# Connector.net
KiCad netlist of a schematic drawn in Altium Designer
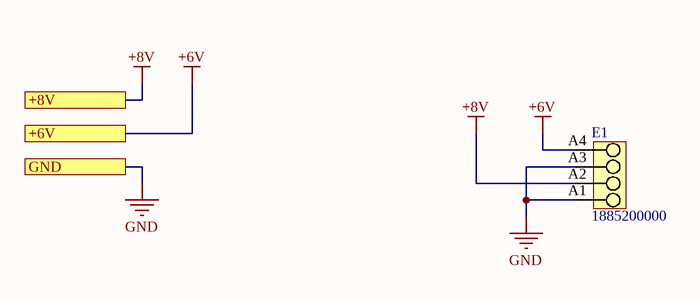
[diagram p0: Connector.SchDoc]

(export (version "E")
  (design (tool "Eeschema 10.0.6"))
  (components
    (comp (ref "E1")
      (value "1885200000")
      (footprint "LSF_SMT_3_5_135_04")
      (description "OMNIMATE Signal - series LSF")
      (fields (field (name "MANUFACTURER") "Weidmueller"))
      (libsource (lib "Altium Content Vault") (part "Terminal_04_1x04"))
    )
  )
  (nets
    (net (code "1") (name "+6V") (class "Default")
      (node (ref "E1") (pin "A4") (pinfunction "A4_A4") (pintype "passive"))
    )
    (net (code "2") (name "+8V") (class "Default")
      (node (ref "E1") (pin "A2") (pinfunction "A2_A2") (pintype "passive"))
    )
    (net (code "3") (name "GND") (class "Default")
      (node (ref "E1") (pin "A1") (pinfunction "A1_A1") (pintype "passive"))
      (node (ref "E1") (pin "A3") (pinfunction "A3_A3") (pintype "passive"))
    )
  )
)
